# BW1098OAK_IMU.net
KiCad netlist of a schematic drawn in Altium Designer
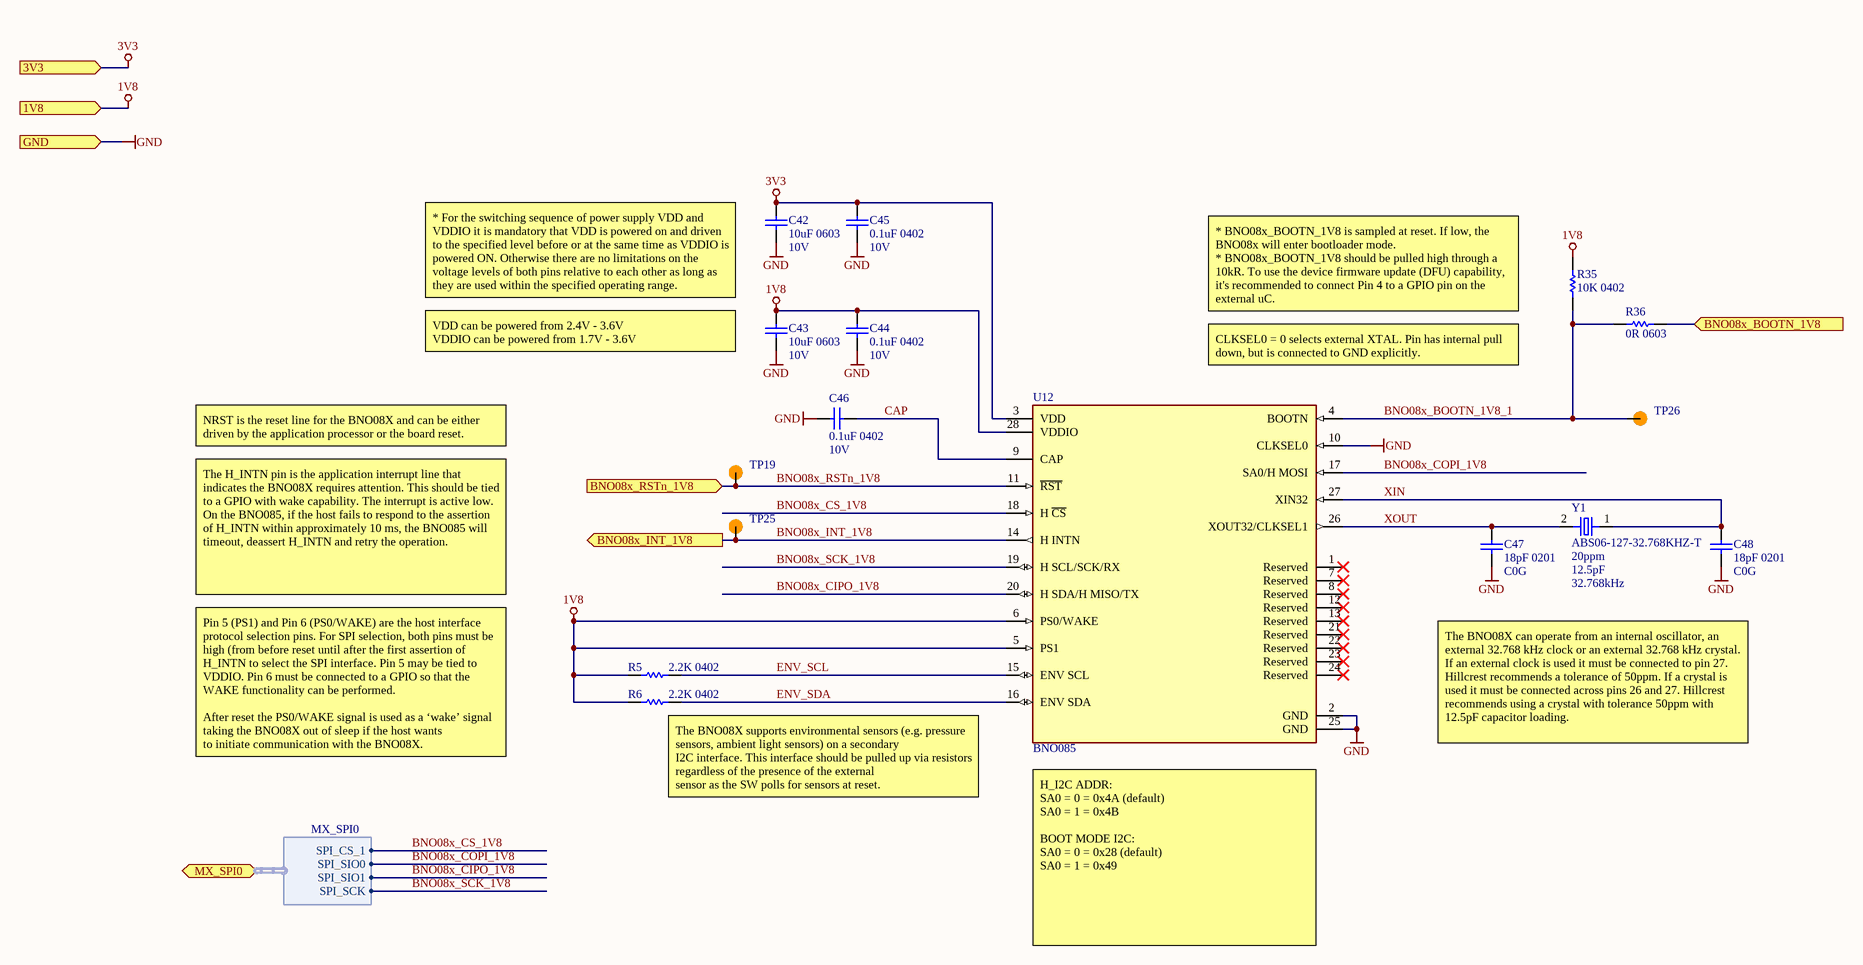
[diagram p0: BW1098OAK_IMU.SchDoc]

(export (version "E")
  (design (tool "Eeschema 10.0.6"))
  (components
    (comp (ref "C42")
      (value "10uF 0603")
      (footprint "CAP_Altium_Vault_Generic:CAPC0603(1608)100_L")
      (description "CAP CER 10UF 10V X5R 0603 20%")
      (fields (field (name "TOLERANCE") "20%") (field (name "VOLTAGE RATING") "10V"))
      (libsource (lib "LuxonisMaster") (part "GRM188R61A106ME69D"))
    )
    (comp (ref "C43")
      (value "10uF 0603")
      (footprint "CAP_Altium_Vault_Generic:CAPC0603(1608)100_L")
      (description "CAP CER 10UF 10V X5R 0603 20%")
      (fields (field (name "TOLERANCE") "20%") (field (name "VOLTAGE RATING") "10V"))
      (libsource (lib "LuxonisMaster") (part "GRM188R61A106ME69D"))
    )
    (comp (ref "C44")
      (value "0.1uF 0402")
      (footprint "CAP_Altium_Vault_Generic:CAPC0402(1005)70_L")
      (description "CAP CER 0.1UF 10V X7R 0402 5%")
      (fields (field (name "TOLERANCE") "5%") (field (name "VOLTAGE RATING") "10V"))
      (libsource (lib "LuxonisMaster") (part "GRM155R71A104JA01D"))
    )
    (comp (ref "C45")
      (value "0.1uF 0402")
      (footprint "CAP_Altium_Vault_Generic:CAPC0402(1005)70_L")
      (description "CAP CER 0.1UF 10V X7R 0402 5%")
      (fields (field (name "TOLERANCE") "5%") (field (name "VOLTAGE RATING") "10V"))
      (libsource (lib "LuxonisMaster") (part "GRM155R71A104JA01D"))
    )
    (comp (ref "C46")
      (value "0.1uF 0402")
      (footprint "CAP_Altium_Vault_Generic:CAPC0402(1005)70_L")
      (description "CAP CER 0.1UF 10V X7R 0402 5%")
      (fields (field (name "TOLERANCE") "5%") (field (name "VOLTAGE RATING") "10V"))
      (libsource (lib "LuxonisMaster") (part "GRM155R71A104JA01D"))
    )
    (comp (ref "C47")
      (value "18pF 0201")
      (footprint "CAP_Altium_Vault_Generic:CAPC0201(0603)33_L")
      (description "Cap Ceramic 18pF 25V C0G 1% Pad SMD 0201 125C T/R")
      (fields (field (name "TOLERANCE") "1%") (field (name "DIELECTRIC") "C0G"))
      (libsource (lib "BW1092_R0M0E0") (part "GRM0335C1E180FA01D"))
    )
    (comp (ref "C48")
      (value "18pF 0201")
      (footprint "CAP_Altium_Vault_Generic:CAPC0201(0603)33_L")
      (description "Cap Ceramic 18pF 25V C0G 1% Pad SMD 0201 125C T/R")
      (fields (field (name "TOLERANCE") "1%") (field (name "DIELECTRIC") "C0G"))
      (libsource (lib "BW1092_R0M0E0") (part "GRM0335C1E180FA01D"))
    )
    (comp (ref "R5")
      (value "2.2K 0402")
      (footprint "RES_Altium_Vault_Generic:RESC0402(1005)_L")
      (description "RES SMD 2.2K OHM 1% 1/16W 0402")
      (fields (field (name "TOLERANCE") "1%"))
      (libsource (lib "LuxonisMaster") (part "RC0402FR-072K2L"))
    )
    (comp (ref "R6")
      (value "2.2K 0402")
      (footprint "RES_Altium_Vault_Generic:RESC0402(1005)_L")
      (description "RES SMD 2.2K OHM 1% 1/16W 0402")
      (fields (field (name "TOLERANCE") "1%"))
      (libsource (lib "LuxonisMaster") (part "RC0402FR-072K2L"))
    )
    (comp (ref "R35")
      (value "10K 0402")
      (footprint "RES_Altium_Vault_Generic:RESC0402(1005)_L")
      (fields (field (name "TOLERANCE") "1%"))
      (libsource (lib "LuxonisMaster") (part "RC0402FR-1310KL"))
    )
    (comp (ref "R36")
      (value "0R 0603")
      (footprint "RES_Altium_Vault_Generic:RESC0603(1608)_L")
      (fields (field (name "TOLERANCE") "5%"))
      (libsource (lib "LuxonisMaster") (part "CRCW06030000Z0EA"))
    )
    (comp (ref "TP19")
      (value "TP100_200_NS")
      (footprint "LuxonisMaster:TP100_200_NS")
      (libsource (lib "LuxonisMaster") (part "TEST_POINT"))
    )
    (comp (ref "TP25")
      (value "TP100_200_NS")
      (footprint "LuxonisMaster:TP100_200_NS")
      (libsource (lib "LuxonisMaster") (part "TEST_POINT"))
    )
    (comp (ref "TP26")
      (value "TP100_200_NS")
      (footprint "LuxonisMaster:TP100_200_NS")
      (libsource (lib "LuxonisMaster") (part "TEST_POINT"))
    )
    (comp (ref "U12")
      (value "BNO085")
      (footprint "BW1092_R0M0E0:BNO085")
      (description "IMU ACCEL/GYRO/MAG I2C 32BIT")
      (libsource (lib "BW1092_R0M0E0") (part "BNO085"))
    )
    (comp (ref "Y1")
      (value "ABS06-127-32.768KHZ-T")
      (footprint "BW1092_R0M0E0:ABS06-127-32.768KHZ-T")
      (description "CRYSTAL 32.768kHz ±20ppm Crystal 12.5pF 90 kOhms 2-SMD, No Lead")
      (fields
        (field (name "FREQUENCY TOLERANCE") "20ppm")
        (field (name "LOAD CAPACITANCE") "12.5pF")
        (field (name "FREQUENCY") "32.768kHz")
      )
      (libsource (lib "BW1092_R0M0E0") (part "ABS06-127-32.768KHZ-T"))
    )
  )
  (nets
    (net (code "2") (name "/BNO08x_BOOTN_1V8") (class "Default")
      (node (ref "R36") (pin "2") (pinfunction "2_2") (pintype "passive"))
    )
    (net (code "3") (name "/BNO08x_BOOTN_1V8_1") (class "Default")
      (node (ref "R35") (pin "1") (pinfunction "1_1") (pintype "passive"))
      (node (ref "R36") (pin "1") (pinfunction "1_1") (pintype "passive"))
      (node (ref "TP26") (pin "1") (pintype "passive"))
      (node (ref "U12") (pin "4") (pinfunction "BOOTN_4") (pintype "input"))
    )
    (net (code "4") (name "/BNO08x_CIPO_1V8") (class "Default")
      (node (ref "U12") (pin "20") (pinfunction "H_SDA/H_MISO/TX_20") (pintype "bidirectional"))
    )
    (net (code "5") (name "/BNO08x_COPI_1V8") (class "Default")
      (node (ref "U12") (pin "17") (pinfunction "SA0/H_MOSI_17") (pintype "input"))
    )
    (net (code "6") (name "/BNO08x_CS_1V8") (class "Default")
      (node (ref "U12") (pin "18") (pinfunction "H_~{CS}_18") (pintype "input"))
    )
    (net (code "7") (name "/BNO08x_INT_1V8") (class "Default")
      (node (ref "TP25") (pin "1") (pintype "passive"))
      (node (ref "U12") (pin "14") (pinfunction "H_INTN_14") (pintype "output"))
    )
    (net (code "8") (name "/BNO08x_RSTn_1V8") (class "Default")
      (node (ref "TP19") (pin "1") (pintype "passive"))
      (node (ref "U12") (pin "11") (pinfunction "~{RST}_11") (pintype "input"))
    )
    (net (code "9") (name "/BNO08x_SCK_1V8") (class "Default")
      (node (ref "U12") (pin "19") (pinfunction "H_SCL/SCK/RX_19") (pintype "bidirectional"))
    )
    (net (code "10") (name "/CAP") (class "Default")
      (node (ref "C46") (pin "1") (pinfunction "1_1") (pintype "passive"))
      (node (ref "U12") (pin "9") (pinfunction "CAP_9") (pintype "passive"))
    )
    (net (code "11") (name "/ENV_SCL") (class "Default")
      (node (ref "R5") (pin "2") (pinfunction "2_2") (pintype "passive"))
      (node (ref "U12") (pin "15") (pinfunction "ENV_SCL_15") (pintype "bidirectional"))
    )
    (net (code "12") (name "/ENV_SDA") (class "Default")
      (node (ref "R6") (pin "2") (pinfunction "2_2") (pintype "passive"))
      (node (ref "U12") (pin "16") (pinfunction "ENV_SDA_16") (pintype "bidirectional"))
    )
    (net (code "13") (name "/XIN") (class "Default")
      (node (ref "C48") (pin "2") (pinfunction "2_2") (pintype "passive"))
      (node (ref "U12") (pin "27") (pinfunction "XIN32_27") (pintype "input"))
      (node (ref "Y1") (pin "1") (pinfunction "1_1") (pintype "passive"))
    )
    (net (code "14") (name "/XOUT") (class "Default")
      (node (ref "C47") (pin "2") (pinfunction "2_2") (pintype "passive"))
      (node (ref "U12") (pin "26") (pinfunction "XOUT32/CLKSEL1_26") (pintype "output"))
      (node (ref "Y1") (pin "2") (pinfunction "2_2") (pintype "passive"))
    )
    (net (code "16") (name "1V8") (class "Default")
      (node (ref "C43") (pin "2") (pinfunction "2_2") (pintype "passive"))
      (node (ref "C44") (pin "2") (pinfunction "2_2") (pintype "passive"))
      (node (ref "R35") (pin "2") (pinfunction "2_2") (pintype "passive"))
      (node (ref "R5") (pin "1") (pinfunction "1_1") (pintype "passive"))
      (node (ref "R6") (pin "1") (pinfunction "1_1") (pintype "passive"))
      (node (ref "U12") (pin "28") (pinfunction "VDDIO_28") (pintype "power_in"))
      (node (ref "U12") (pin "5") (pinfunction "PS1_5") (pintype "input"))
      (node (ref "U12") (pin "6") (pinfunction "PS0/WAKE_6") (pintype "input"))
    )
    (net (code "17") (name "3V3") (class "Default")
      (node (ref "C42") (pin "2") (pinfunction "2_2") (pintype "passive"))
      (node (ref "C45") (pin "2") (pinfunction "2_2") (pintype "passive"))
      (node (ref "U12") (pin "3") (pinfunction "VDD_3") (pintype "power_in"))
    )
    (net (code "18") (name "GND") (class "Default")
      (node (ref "C42") (pin "1") (pinfunction "1_1") (pintype "passive"))
      (node (ref "C43") (pin "1") (pinfunction "1_1") (pintype "passive"))
      (node (ref "C44") (pin "1") (pinfunction "1_1") (pintype "passive"))
      (node (ref "C45") (pin "1") (pinfunction "1_1") (pintype "passive"))
      (node (ref "C46") (pin "2") (pinfunction "2_2") (pintype "passive"))
      (node (ref "C47") (pin "1") (pinfunction "1_1") (pintype "passive"))
      (node (ref "C48") (pin "1") (pinfunction "1_1") (pintype "passive"))
      (node (ref "U12") (pin "10") (pinfunction "CLKSEL0_10") (pintype "input"))
      (node (ref "U12") (pin "2") (pinfunction "GND_2") (pintype "power_in"))
      (node (ref "U12") (pin "25") (pinfunction "GND_25") (pintype "power_in"))
    )
    (net (code "19") (name "unconnected-(U12-Reserved-Pad1)") (class "Default")
      (node (ref "U12") (pin "1") (pinfunction "Reserved_1") (pintype "passive+no_connect"))
    )
    (net (code "20") (name "unconnected-(U12-Reserved-Pad7)") (class "Default")
      (node (ref "U12") (pin "7") (pinfunction "Reserved_7") (pintype "passive+no_connect"))
    )
    (net (code "21") (name "unconnected-(U12-Reserved-Pad8)") (class "Default")
      (node (ref "U12") (pin "8") (pinfunction "Reserved_8") (pintype "passive+no_connect"))
    )
    (net (code "22") (name "unconnected-(U12-Reserved-Pad12)") (class "Default")
      (node (ref "U12") (pin "12") (pinfunction "Reserved_12") (pintype "passive+no_connect"))
    )
    (net (code "23") (name "unconnected-(U12-Reserved-Pad13)") (class "Default")
      (node (ref "U12") (pin "13") (pinfunction "Reserved_13") (pintype "passive+no_connect"))
    )
    (net (code "24") (name "unconnected-(U12-Reserved-Pad21)") (class "Default")
      (node (ref "U12") (pin "21") (pinfunction "Reserved_21") (pintype "passive+no_connect"))
    )
    (net (code "25") (name "unconnected-(U12-Reserved-Pad22)") (class "Default")
      (node (ref "U12") (pin "22") (pinfunction "Reserved_22") (pintype "passive+no_connect"))
    )
    (net (code "26") (name "unconnected-(U12-Reserved-Pad23)") (class "Default")
      (node (ref "U12") (pin "23") (pinfunction "Reserved_23") (pintype "passive+no_connect"))
    )
    (net (code "27") (name "unconnected-(U12-Reserved-Pad24)") (class "Default")
      (node (ref "U12") (pin "24") (pinfunction "Reserved_24") (pintype "passive+no_connect"))
    )
  )
)
